# Motor_Driver.net
KiCad netlist of a schematic drawn in Altium Designer
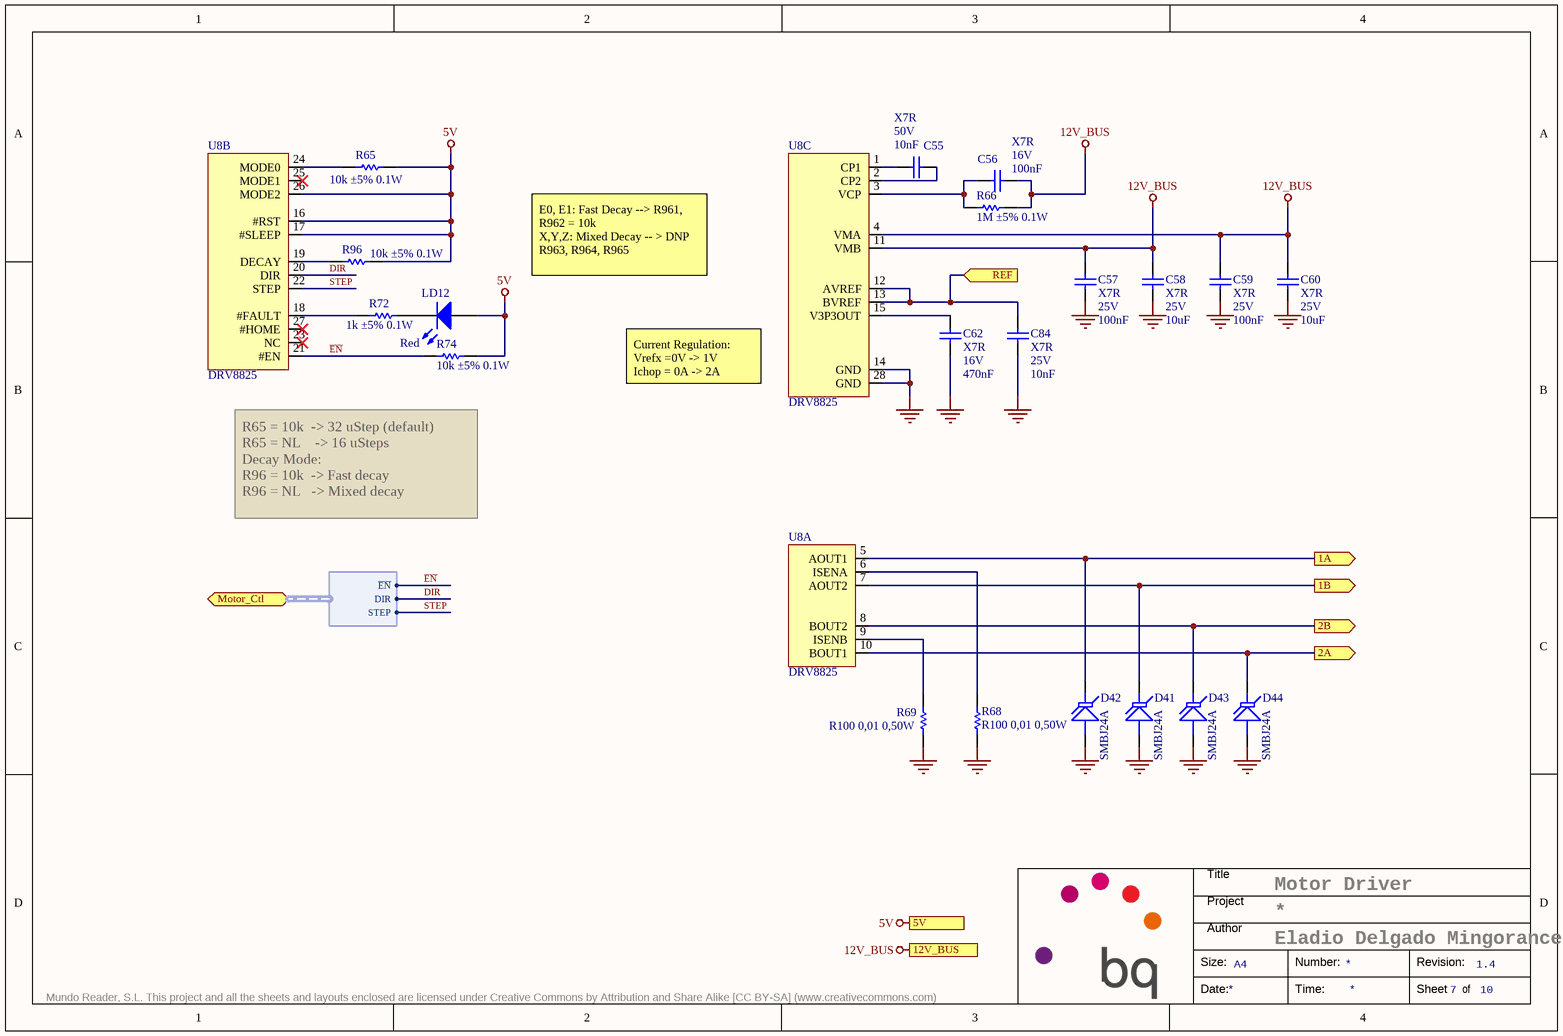
[diagram p0: Motor_Driver.SchDoc]

(export (version "E")
  (design (tool "Eeschema 10.0.6"))
  (components
    (comp (ref "C55")
      (value "Capacitor")
      (footprint "C0805")
      (description "Capacitor SMD")
      (fields
        (field (name "DIELECTRIC") "X7R")
        (field (name "VOLTAGE") "50V")
        (field (name "CAPACITANCE") "10nF")
        (field (name "PART NUMBER") "C0805_10nF_50V_±10%")
        (field (name "TOLERANCE") "±10%")
      )
      (libsource (lib "Pasives_Capacitor_SMD") (part "Capacitor"))
    )
    (comp (ref "C56")
      (value "Capacitor")
      (footprint "C0603")
      (description "Capacitor SMD")
      (fields
        (field (name "DIELECTRIC") "X7R")
        (field (name "VOLTAGE") "16V")
        (field (name "CAPACITANCE") "100nF")
        (field (name "PART NUMBER") "C0603_100nF_16V_±10%")
        (field (name "TOLERANCE") "±10%")
      )
      (libsource (lib "Pasives_Capacitor_SMD") (part "Capacitor"))
    )
    (comp (ref "C57")
      (value "Capacitor")
      (footprint "C0603")
      (description "Capacitor SMD")
      (fields
        (field (name "DIELECTRIC") "X7R")
        (field (name "VOLTAGE") "25V")
        (field (name "CAPACITANCE") "100nF")
        (field (name "PART NUMBER") "C0603_100nF_25V_±10%")
        (field (name "TOLERANCE") "±10%")
      )
      (libsource (lib "Pasives_Capacitor_SMD") (part "Capacitor"))
    )
    (comp (ref "C58")
      (value "Capacitor")
      (footprint "C1206")
      (description "Capacitor SMD")
      (fields
        (field (name "DIELECTRIC") "X7R")
        (field (name "VOLTAGE") "25V")
        (field (name "CAPACITANCE") "10uF")
        (field (name "PART NUMBER") "C1206_10uF_25V_±10%")
        (field (name "TOLERANCE") "±10%")
      )
      (libsource (lib "Pasives_Capacitor_SMD") (part "Capacitor"))
    )
    (comp (ref "C59")
      (value "Capacitor")
      (footprint "C0603")
      (description "Capacitor SMD")
      (fields
        (field (name "DIELECTRIC") "X7R")
        (field (name "VOLTAGE") "25V")
        (field (name "CAPACITANCE") "100nF")
        (field (name "PART NUMBER") "C0603_100nF_25V_±10%")
        (field (name "TOLERANCE") "±10%")
      )
      (libsource (lib "Pasives_Capacitor_SMD") (part "Capacitor"))
    )
    (comp (ref "C60")
      (value "Capacitor")
      (footprint "C1206")
      (description "Capacitor SMD")
      (fields
        (field (name "DIELECTRIC") "X7R")
        (field (name "VOLTAGE") "25V")
        (field (name "CAPACITANCE") "10uF")
        (field (name "PART NUMBER") "C1206_10uF_25V_±10%")
        (field (name "TOLERANCE") "±10%")
      )
      (libsource (lib "Pasives_Capacitor_SMD") (part "Capacitor"))
    )
    (comp (ref "C62")
      (value "Capacitor")
      (footprint "C0603")
      (description "Capacitor SMD")
      (fields
        (field (name "DIELECTRIC") "X7R")
        (field (name "VOLTAGE") "16V")
        (field (name "CAPACITANCE") "470nF")
        (field (name "PART NUMBER") "C0603_470nF_16V_±10%")
        (field (name "TOLERANCE") "±10%")
      )
      (libsource (lib "Pasives_Capacitor_SMD") (part "Capacitor"))
    )
    (comp (ref "C84")
      (value "Capacitor")
      (footprint "C0603")
      (description "Capacitor SMD")
      (fields
        (field (name "DIELECTRIC") "X7R")
        (field (name "VOLTAGE") "25V")
        (field (name "CAPACITANCE") "10nF")
        (field (name "PART NUMBER") "C0603_10nF_25V_±10%")
        (field (name "TOLERANCE") "±10%")
      )
      (libsource (lib "Pasives_Capacitor_SMD") (part "Capacitor"))
    )
    (comp (ref "D41")
      (value "SMBJ24A")
      (footprint "DO-214AA")
      (description "Transient Suppression Diodes")
      (fields (field (name "PART NUMBER") "TVS 24Vdc") (field (name "VOLTAGE") "24Vdc"))
      (libsource (lib "Protection") (part "Zener_TVS"))
    )
    (comp (ref "D42")
      (value "SMBJ24A")
      (footprint "DO-214AA")
      (description "Transient Suppression Diodes")
      (fields (field (name "PART NUMBER") "TVS 24Vdc") (field (name "VOLTAGE") "24Vdc"))
      (libsource (lib "Protection") (part "Zener_TVS"))
    )
    (comp (ref "D43")
      (value "SMBJ24A")
      (footprint "DO-214AA")
      (description "Transient Suppression Diodes")
      (fields (field (name "PART NUMBER") "TVS 24Vdc") (field (name "VOLTAGE") "24Vdc"))
      (libsource (lib "Protection") (part "Zener_TVS"))
    )
    (comp (ref "D44")
      (value "SMBJ24A")
      (footprint "DO-214AA")
      (description "Transient Suppression Diodes")
      (fields (field (name "PART NUMBER") "TVS 24Vdc") (field (name "VOLTAGE") "24Vdc"))
      (libsource (lib "Protection") (part "Zener_TVS"))
    )
    (comp (ref "LD12")
      (value "Red")
      (footprint "LED0603")
      (description "LED")
      (fields (field (name "PART NUMBER") "HSMH-C190") (field (name "MANUFACTURER") "Avago Technologies"))
      (libsource (lib "Optoelectronics") (part "LED"))
    )
    (comp (ref "R65")
      (value "10k ±5% 0.1W")
      (footprint "R0603")
      (description "Resistor, SMD")
      (fields (field (name "TOLERANCE") "±5%") (field (name "POWER") "0.1W"))
      (libsource (lib "Pasives_Resistor_SMD") (part "Resistor"))
    )
    (comp (ref "R66")
      (value "1M ±5% 0.1W")
      (footprint "R0603")
      (description "Resistor, SMD")
      (fields (field (name "TOLERANCE") "±5%") (field (name "POWER") "0.1W"))
      (libsource (lib "Pasives_Resistor_SMD") (part "Resistor"))
    )
    (comp (ref "R68")
      (value "R100 0,01 0,50W")
      (footprint "R1206")
      (description "Resistor, current sensor")
      (fields (field (name "TOLERANCE") "0,01") (field (name "POWER") "0,50W"))
      (libsource (lib "Pasives_Current_Sensor_Resistor") (part "Resistor"))
    )
    (comp (ref "R69")
      (value "R100 0,01 0,50W")
      (footprint "R1206")
      (description "Resistor, current sensor")
      (fields (field (name "TOLERANCE") "0,01") (field (name "POWER") "0,50W"))
      (libsource (lib "Pasives_Current_Sensor_Resistor") (part "Resistor"))
    )
    (comp (ref "R72")
      (value "1k ±5% 0.1W")
      (footprint "R0603")
      (description "Resistor, SMD")
      (fields (field (name "TOLERANCE") "±5%") (field (name "POWER") "0.1W"))
      (libsource (lib "Pasives_Resistor_SMD") (part "Resistor"))
    )
    (comp (ref "R74")
      (value "10k ±5% 0.1W")
      (footprint "R0603")
      (description "Resistor, SMD")
      (fields (field (name "TOLERANCE") "±5%") (field (name "POWER") "0.1W"))
      (libsource (lib "Pasives_Resistor_SMD") (part "Resistor"))
    )
    (comp (ref "R96")
      (value "10k ±5% 0.1W")
      (footprint "R0603")
      (description "Resistor, SMD")
      (fields (field (name "TOLERANCE") "±5%") (field (name "POWER") "0.1W"))
      (libsource (lib "Pasives_Resistor_SMD") (part "Resistor"))
    )
    (comp (ref "U8")
      (value "DRV8825")
      (footprint "SOP28")
      (description "Stepper Motor Controller IC")
      (fields (field (name "MANUFACTURER") "Texas Instruments"))
      (libsource (lib "Power_Motor") (part "DRV8825"))
    )
  )
  (nets
    (net (code "2") (name "/1A") (class "Default")
      (node (ref "D42") (pin "K") (pinfunction "K_K") (pintype "passive"))
      (node (ref "U8") (pin "5") (pinfunction "AOUT1_5") (pintype "passive"))
    )
    (net (code "3") (name "/1B") (class "Default")
      (node (ref "D41") (pin "K") (pinfunction "K_K") (pintype "passive"))
      (node (ref "U8") (pin "7") (pinfunction "AOUT2_7") (pintype "passive"))
    )
    (net (code "4") (name "/2A") (class "Default")
      (node (ref "D44") (pin "K") (pinfunction "K_K") (pintype "passive"))
      (node (ref "U8") (pin "10") (pinfunction "BOUT1_10") (pintype "passive"))
    )
    (net (code "5") (name "/2B") (class "Default")
      (node (ref "D43") (pin "K") (pinfunction "K_K") (pintype "passive"))
      (node (ref "U8") (pin "8") (pinfunction "BOUT2_8") (pintype "passive"))
    )
    (net (code "6") (name "/DIR") (class "Default")
      (node (ref "U8") (pin "20") (pinfunction "DIR_20") (pintype "passive"))
    )
    (net (code "7") (name "/EN") (class "Default")
      (node (ref "R74") (pin "1") (pinfunction "1_1") (pintype "passive"))
      (node (ref "U8") (pin "21") (pinfunction "#EN_21") (pintype "passive"))
    )
    (net (code "8") (name "/REF") (class "Default")
      (node (ref "C84") (pin "2") (pinfunction "2_2") (pintype "passive"))
      (node (ref "U8") (pin "12") (pinfunction "AVREF_12") (pintype "passive"))
      (node (ref "U8") (pin "13") (pinfunction "BVREF_13") (pintype "passive"))
    )
    (net (code "9") (name "/STEP") (class "Default")
      (node (ref "U8") (pin "22") (pinfunction "STEP_22") (pintype "passive"))
    )
    (net (code "11") (name "5V") (class "Default")
      (node (ref "LD12") (pin "A") (pinfunction "A_A") (pintype "passive"))
      (node (ref "R65") (pin "1") (pinfunction "1_1") (pintype "passive"))
      (node (ref "R74") (pin "2") (pinfunction "2_2") (pintype "passive"))
      (node (ref "R96") (pin "1") (pinfunction "1_1") (pintype "passive"))
      (node (ref "U8") (pin "16") (pinfunction "#RST_16") (pintype "passive"))
      (node (ref "U8") (pin "17") (pinfunction "#SLEEP_17") (pintype "passive"))
      (node (ref "U8") (pin "26") (pinfunction "MODE2_26") (pintype "passive"))
    )
    (net (code "12") (name "12V_BUS") (class "Default")
      (node (ref "C56") (pin "1") (pinfunction "1_1") (pintype "passive"))
      (node (ref "C57") (pin "2") (pinfunction "2_2") (pintype "passive"))
      (node (ref "C58") (pin "2") (pinfunction "2_2") (pintype "passive"))
      (node (ref "C59") (pin "2") (pinfunction "2_2") (pintype "passive"))
      (node (ref "C60") (pin "2") (pinfunction "2_2") (pintype "passive"))
      (node (ref "R66") (pin "2") (pinfunction "2_2") (pintype "passive"))
      (node (ref "U8") (pin "11") (pinfunction "VMB_11") (pintype "passive"))
      (node (ref "U8") (pin "4") (pinfunction "VMA_4") (pintype "passive"))
    )
    (net (code "13") (name "GND") (class "Default")
      (node (ref "C57") (pin "1") (pinfunction "1_1") (pintype "passive"))
      (node (ref "C58") (pin "1") (pinfunction "1_1") (pintype "passive"))
      (node (ref "C59") (pin "1") (pinfunction "1_1") (pintype "passive"))
      (node (ref "C60") (pin "1") (pinfunction "1_1") (pintype "passive"))
      (node (ref "C62") (pin "1") (pinfunction "1_1") (pintype "passive"))
      (node (ref "C84") (pin "1") (pinfunction "1_1") (pintype "passive"))
      (node (ref "D41") (pin "A") (pinfunction "A_A") (pintype "passive"))
      (node (ref "D42") (pin "A") (pinfunction "A_A") (pintype "passive"))
      (node (ref "D43") (pin "A") (pinfunction "A_A") (pintype "passive"))
      (node (ref "D44") (pin "A") (pinfunction "A_A") (pintype "passive"))
      (node (ref "R68") (pin "1") (pinfunction "1_1") (pintype "passive"))
      (node (ref "R69") (pin "1") (pinfunction "1_1") (pintype "passive"))
      (node (ref "U8") (pin "14") (pinfunction "GND_14") (pintype "passive"))
      (node (ref "U8") (pin "28") (pinfunction "GND_28") (pintype "passive"))
    )
    (net (code "14") (name "Net-(LD12-PadK)") (class "Default")
      (node (ref "LD12") (pin "K") (pinfunction "K_K") (pintype "passive"))
      (node (ref "R72") (pin "2") (pinfunction "2_2") (pintype "passive"))
    )
    (net (code "15") (name "Net-(U8A-ISENA)") (class "Default")
      (node (ref "R68") (pin "2") (pinfunction "2_2") (pintype "passive"))
      (node (ref "U8") (pin "6") (pinfunction "ISENA_6") (pintype "passive"))
    )
    (net (code "16") (name "Net-(U8A-ISENB)") (class "Default")
      (node (ref "R69") (pin "2") (pinfunction "2_2") (pintype "passive"))
      (node (ref "U8") (pin "9") (pinfunction "ISENB_9") (pintype "passive"))
    )
    (net (code "17") (name "Net-(U8B-#FAULT)") (class "Default")
      (node (ref "R72") (pin "1") (pinfunction "1_1") (pintype "passive"))
      (node (ref "U8") (pin "18") (pinfunction "#FAULT_18") (pintype "passive"))
    )
    (net (code "18") (name "Net-(U8B-DECAY)") (class "Default")
      (node (ref "R96") (pin "2") (pinfunction "2_2") (pintype "passive"))
      (node (ref "U8") (pin "19") (pinfunction "DECAY_19") (pintype "passive"))
    )
    (net (code "19") (name "Net-(U8B-MODE0)") (class "Default")
      (node (ref "R65") (pin "2") (pinfunction "2_2") (pintype "passive"))
      (node (ref "U8") (pin "24") (pinfunction "MODE0_24") (pintype "passive"))
    )
    (net (code "20") (name "Net-(U8C-CP1)") (class "Default")
      (node (ref "C55") (pin "2") (pinfunction "2_2") (pintype "passive"))
      (node (ref "U8") (pin "1") (pinfunction "CP1_1") (pintype "passive"))
    )
    (net (code "21") (name "Net-(U8C-CP2)") (class "Default")
      (node (ref "C55") (pin "1") (pinfunction "1_1") (pintype "passive"))
      (node (ref "U8") (pin "2") (pinfunction "CP2_2") (pintype "passive"))
    )
    (net (code "22") (name "Net-(U8C-V3P3OUT)") (class "Default")
      (node (ref "C62") (pin "2") (pinfunction "2_2") (pintype "passive"))
      (node (ref "U8") (pin "15") (pinfunction "V3P3OUT_15") (pintype "passive"))
    )
    (net (code "23") (name "Net-(U8C-VCP)") (class "Default")
      (node (ref "C56") (pin "2") (pinfunction "2_2") (pintype "passive"))
      (node (ref "R66") (pin "1") (pinfunction "1_1") (pintype "passive"))
      (node (ref "U8") (pin "3") (pinfunction "VCP_3") (pintype "passive"))
    )
    (net (code "24") (name "unconnected-(U8B-#HOME-Pad27)") (class "Default")
      (node (ref "U8") (pin "27") (pinfunction "#HOME_27") (pintype "passive+no_connect"))
    )
    (net (code "25") (name "unconnected-(U8B-MODE1-Pad25)") (class "Default")
      (node (ref "U8") (pin "25") (pinfunction "MODE1_25") (pintype "passive+no_connect"))
    )
    (net (code "26") (name "unconnected-(U8B-NC-Pad23)") (class "Default")
      (node (ref "U8") (pin "23") (pinfunction "NC_23") (pintype "passive+no_connect"))
    )
  )
)
